# rectificador.net
KiCad netlist of a schematic drawn in EAGLE
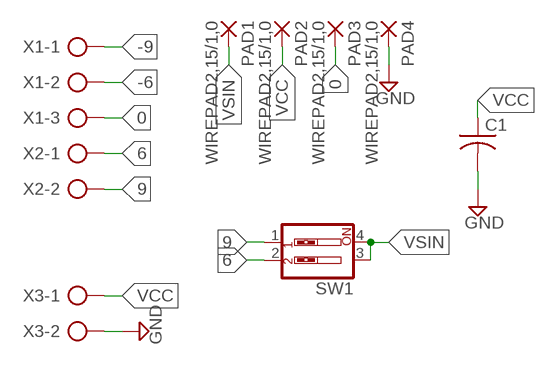
[diagram p0: schematic, sheet 1]

(export (version "E")
  (design (tool "Eeschema 10.0.6"))
  (components
    (comp (ref "C1")
      (value "C-US050-024X044")
      (footprint "eagle-import:C050-024X044")
      (libsource (lib "eagle-import") (part "C-US050-024X044"))
    )
    (comp (ref "PAD1")
      (value "WIREPAD2,15/1,0")
      (footprint "eagle-import:2,15_1,0")
      (libsource (lib "eagle-import") (part "WIREPAD2,15/1,0"))
    )
    (comp (ref "PAD2")
      (value "WIREPAD2,15/1,0")
      (footprint "eagle-import:2,15_1,0")
      (libsource (lib "eagle-import") (part "WIREPAD2,15/1,0"))
    )
    (comp (ref "PAD3")
      (value "WIREPAD2,15/1,0")
      (footprint "eagle-import:2,15_1,0")
      (libsource (lib "eagle-import") (part "WIREPAD2,15/1,0"))
    )
    (comp (ref "PAD4")
      (value "WIREPAD2,15/1,0")
      (footprint "eagle-import:2,15_1,0")
      (libsource (lib "eagle-import") (part "WIREPAD2,15/1,0"))
    )
    (comp (ref "SW1")
      (value "SW_DIP-2")
      (footprint "eagle-import:EDG-02")
      (libsource (lib "eagle-import") (part "SW_DIP-2"))
    )
    (comp (ref "X1")
      (value "AK300/3")
      (footprint "eagle-import:AK300_3")
      (libsource (lib "eagle-import") (part "AK300/3"))
    )
    (comp (ref "X2")
      (value "AK300/2")
      (footprint "eagle-import:AK300_2")
      (libsource (lib "eagle-import") (part "AK300/2"))
    )
    (comp (ref "X3")
      (value "AK300/2")
      (footprint "eagle-import:AK300_2")
      (libsource (lib "eagle-import") (part "AK300/2"))
    )
  )
  (nets
    (net (code "1") (name "-6") (class "Default")
      (node (ref "X1") (pin "2") (pinfunction "KL_2") (pintype "passive"))
    )
    (net (code "2") (name "-9") (class "Default")
      (node (ref "X1") (pin "1") (pinfunction "KL_1") (pintype "passive"))
    )
    (net (code "3") (name "0") (class "Default")
      (node (ref "PAD3") (pin "1") (pinfunction "P_1") (pintype "passive"))
      (node (ref "X1") (pin "3") (pinfunction "KL_3") (pintype "passive"))
    )
    (net (code "4") (name "6") (class "Default")
      (node (ref "SW1") (pin "2") (pinfunction "2_2") (pintype "passive"))
      (node (ref "X2") (pin "1") (pinfunction "KL_1") (pintype "passive"))
    )
    (net (code "5") (name "9") (class "Default")
      (node (ref "SW1") (pin "1") (pinfunction "1_1") (pintype "passive"))
      (node (ref "X2") (pin "2") (pinfunction "KL_2") (pintype "passive"))
    )
    (net (code "6") (name "GND") (class "Default")
      (node (ref "C1") (pin "2") (pinfunction "2_2") (pintype "passive"))
      (node (ref "PAD4") (pin "1") (pinfunction "P_1") (pintype "passive"))
      (node (ref "X3") (pin "2") (pinfunction "KL_2") (pintype "passive"))
    )
    (net (code "7") (name "VCC") (class "Default")
      (node (ref "C1") (pin "1") (pinfunction "1_1") (pintype "passive"))
      (node (ref "PAD2") (pin "1") (pinfunction "P_1") (pintype "passive"))
      (node (ref "X3") (pin "1") (pinfunction "KL_1") (pintype "passive"))
    )
    (net (code "8") (name "VSIN") (class "Default")
      (node (ref "PAD1") (pin "1") (pinfunction "P_1") (pintype "passive"))
      (node (ref "SW1") (pin "3") (pinfunction "3_3") (pintype "passive"))
      (node (ref "SW1") (pin "4") (pinfunction "4_4") (pintype "passive"))
    )
  )
)
